# BOC_IO.net
KiCad netlist of a schematic drawn in Altium Designer
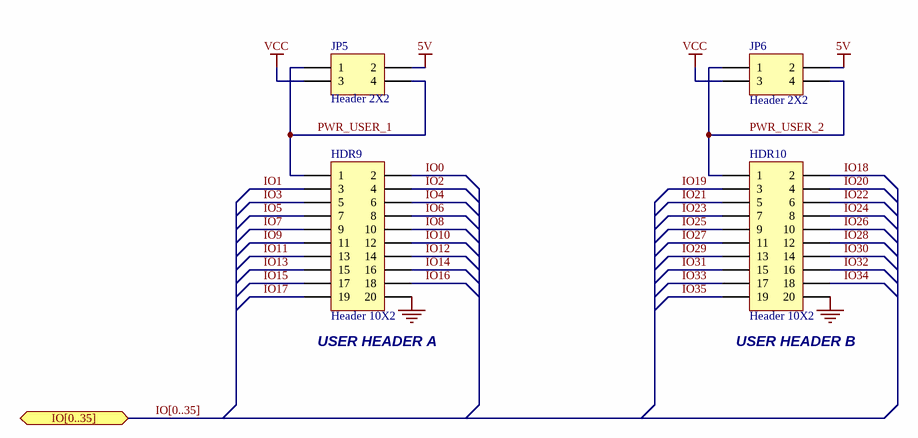
[diagram p0: BOC_IO.SchDoc]

(export (version "E")
  (design (tool "Eeschema 10.0.6"))
  (components
    (comp (ref "HDR9")
      (value "Header 10X2")
      (footprint "Altium Nanoboard Project:HDR2X10")
      (description "Header, 10-Pin, Dual row")
      (fields (field (name "MANUFACTURER") "Generic Components") (field (name "PUBLISHER") "Altium Limited"))
      (libsource (lib "Altium Nanoboard Project") (part "Header 10X2"))
    )
    (comp (ref "HDR10")
      (value "Header 10X2")
      (footprint "Altium Nanoboard Project:HDR2X10")
      (description "Header, 10-Pin, Dual row")
      (fields (field (name "MANUFACTURER") "Generic Components") (field (name "PUBLISHER") "Altium Limited"))
      (libsource (lib "Altium Nanoboard Project") (part "Header 10X2"))
    )
    (comp (ref "JP5")
      (value "Header 2X2")
      (footprint "Altium Nanoboard Project:HDR2X2_B")
      (description "Header, 2-Pin, Dual row")
      (fields (field (name "MANUFACTURER") "Generic Components") (field (name "PUBLISHER") "Altium Limited"))
      (libsource (lib "Altium Nanoboard Project") (part "Header 2X2"))
    )
    (comp (ref "JP6")
      (value "Header 2X2")
      (footprint "Altium Nanoboard Project:HDR2X2_B")
      (description "Header, 2-Pin, Dual row")
      (fields (field (name "MANUFACTURER") "Generic Components") (field (name "PUBLISHER") "Altium Limited"))
      (libsource (lib "Altium Nanoboard Project") (part "Header 2X2"))
    )
  )
  (nets
    (net (code "1") (name "/IO0") (class "Default")
      (node (ref "HDR9") (pin "2") (pinfunction "2_2") (pintype "passive"))
    )
    (net (code "2") (name "/IO1") (class "Default")
      (node (ref "HDR9") (pin "3") (pinfunction "3_3") (pintype "passive"))
    )
    (net (code "3") (name "/IO2") (class "Default")
      (node (ref "HDR9") (pin "4") (pinfunction "4_4") (pintype "passive"))
    )
    (net (code "4") (name "/IO3") (class "Default")
      (node (ref "HDR9") (pin "5") (pinfunction "5_5") (pintype "passive"))
    )
    (net (code "5") (name "/IO4") (class "Default")
      (node (ref "HDR9") (pin "6") (pinfunction "6_6") (pintype "passive"))
    )
    (net (code "6") (name "/IO5") (class "Default")
      (node (ref "HDR9") (pin "7") (pinfunction "7_7") (pintype "passive"))
    )
    (net (code "7") (name "/IO6") (class "Default")
      (node (ref "HDR9") (pin "8") (pinfunction "8_8") (pintype "passive"))
    )
    (net (code "8") (name "/IO7") (class "Default")
      (node (ref "HDR9") (pin "9") (pinfunction "9_9") (pintype "passive"))
    )
    (net (code "9") (name "/IO8") (class "Default")
      (node (ref "HDR9") (pin "10") (pinfunction "10_10") (pintype "passive"))
    )
    (net (code "10") (name "/IO9") (class "Default")
      (node (ref "HDR9") (pin "11") (pinfunction "11_11") (pintype "passive"))
    )
    (net (code "11") (name "/IO10") (class "Default")
      (node (ref "HDR9") (pin "12") (pinfunction "12_12") (pintype "passive"))
    )
    (net (code "12") (name "/IO11") (class "Default")
      (node (ref "HDR9") (pin "13") (pinfunction "13_13") (pintype "passive"))
    )
    (net (code "13") (name "/IO12") (class "Default")
      (node (ref "HDR9") (pin "14") (pinfunction "14_14") (pintype "passive"))
    )
    (net (code "14") (name "/IO13") (class "Default")
      (node (ref "HDR9") (pin "15") (pinfunction "15_15") (pintype "passive"))
    )
    (net (code "15") (name "/IO14") (class "Default")
      (node (ref "HDR9") (pin "16") (pinfunction "16_16") (pintype "passive"))
    )
    (net (code "16") (name "/IO15") (class "Default")
      (node (ref "HDR9") (pin "17") (pinfunction "17_17") (pintype "passive"))
    )
    (net (code "17") (name "/IO16") (class "Default")
      (node (ref "HDR9") (pin "18") (pinfunction "18_18") (pintype "passive"))
    )
    (net (code "18") (name "/IO17") (class "Default")
      (node (ref "HDR9") (pin "19") (pinfunction "19_19") (pintype "passive"))
    )
    (net (code "19") (name "/IO18") (class "Default")
      (node (ref "HDR10") (pin "2") (pinfunction "2_2") (pintype "passive"))
    )
    (net (code "20") (name "/IO19") (class "Default")
      (node (ref "HDR10") (pin "3") (pinfunction "3_3") (pintype "passive"))
    )
    (net (code "21") (name "/IO20") (class "Default")
      (node (ref "HDR10") (pin "4") (pinfunction "4_4") (pintype "passive"))
    )
    (net (code "22") (name "/IO21") (class "Default")
      (node (ref "HDR10") (pin "5") (pinfunction "5_5") (pintype "passive"))
    )
    (net (code "23") (name "/IO22") (class "Default")
      (node (ref "HDR10") (pin "6") (pinfunction "6_6") (pintype "passive"))
    )
    (net (code "24") (name "/IO23") (class "Default")
      (node (ref "HDR10") (pin "7") (pinfunction "7_7") (pintype "passive"))
    )
    (net (code "25") (name "/IO24") (class "Default")
      (node (ref "HDR10") (pin "8") (pinfunction "8_8") (pintype "passive"))
    )
    (net (code "26") (name "/IO25") (class "Default")
      (node (ref "HDR10") (pin "9") (pinfunction "9_9") (pintype "passive"))
    )
    (net (code "27") (name "/IO26") (class "Default")
      (node (ref "HDR10") (pin "10") (pinfunction "10_10") (pintype "passive"))
    )
    (net (code "28") (name "/IO27") (class "Default")
      (node (ref "HDR10") (pin "11") (pinfunction "11_11") (pintype "passive"))
    )
    (net (code "29") (name "/IO28") (class "Default")
      (node (ref "HDR10") (pin "12") (pinfunction "12_12") (pintype "passive"))
    )
    (net (code "30") (name "/IO29") (class "Default")
      (node (ref "HDR10") (pin "13") (pinfunction "13_13") (pintype "passive"))
    )
    (net (code "31") (name "/IO30") (class "Default")
      (node (ref "HDR10") (pin "14") (pinfunction "14_14") (pintype "passive"))
    )
    (net (code "32") (name "/IO31") (class "Default")
      (node (ref "HDR10") (pin "15") (pinfunction "15_15") (pintype "passive"))
    )
    (net (code "33") (name "/IO32") (class "Default")
      (node (ref "HDR10") (pin "16") (pinfunction "16_16") (pintype "passive"))
    )
    (net (code "34") (name "/IO33") (class "Default")
      (node (ref "HDR10") (pin "17") (pinfunction "17_17") (pintype "passive"))
    )
    (net (code "35") (name "/IO34") (class "Default")
      (node (ref "HDR10") (pin "18") (pinfunction "18_18") (pintype "passive"))
    )
    (net (code "36") (name "/IO35") (class "Default")
      (node (ref "HDR10") (pin "19") (pinfunction "19_19") (pintype "passive"))
    )
    (net (code "38") (name "/PWR_USER_1") (class "Default")
      (node (ref "HDR9") (pin "1") (pinfunction "1_1") (pintype "passive"))
      (node (ref "JP5") (pin "1") (pinfunction "1_1") (pintype "passive"))
      (node (ref "JP5") (pin "4") (pinfunction "4_4") (pintype "passive"))
    )
    (net (code "39") (name "/PWR_USER_2") (class "Default")
      (node (ref "HDR10") (pin "1") (pinfunction "1_1") (pintype "passive"))
      (node (ref "JP6") (pin "1") (pinfunction "1_1") (pintype "passive"))
      (node (ref "JP6") (pin "4") (pinfunction "4_4") (pintype "passive"))
    )
    (net (code "40") (name "5V") (class "Default")
      (node (ref "JP5") (pin "2") (pinfunction "2_2") (pintype "passive"))
      (node (ref "JP6") (pin "2") (pinfunction "2_2") (pintype "passive"))
    )
    (net (code "41") (name "GND") (class "Default")
      (node (ref "HDR10") (pin "20") (pinfunction "20_20") (pintype "passive"))
      (node (ref "HDR9") (pin "20") (pinfunction "20_20") (pintype "passive"))
    )
    (net (code "42") (name "VCC") (class "Default")
      (node (ref "JP5") (pin "3") (pinfunction "3_3") (pintype "passive"))
      (node (ref "JP6") (pin "3") (pinfunction "3_3") (pintype "passive"))
    )
  )
)
